# JacdacEc30Hub10x40_114.net
KiCad netlist of a schematic drawn in Altium Designer
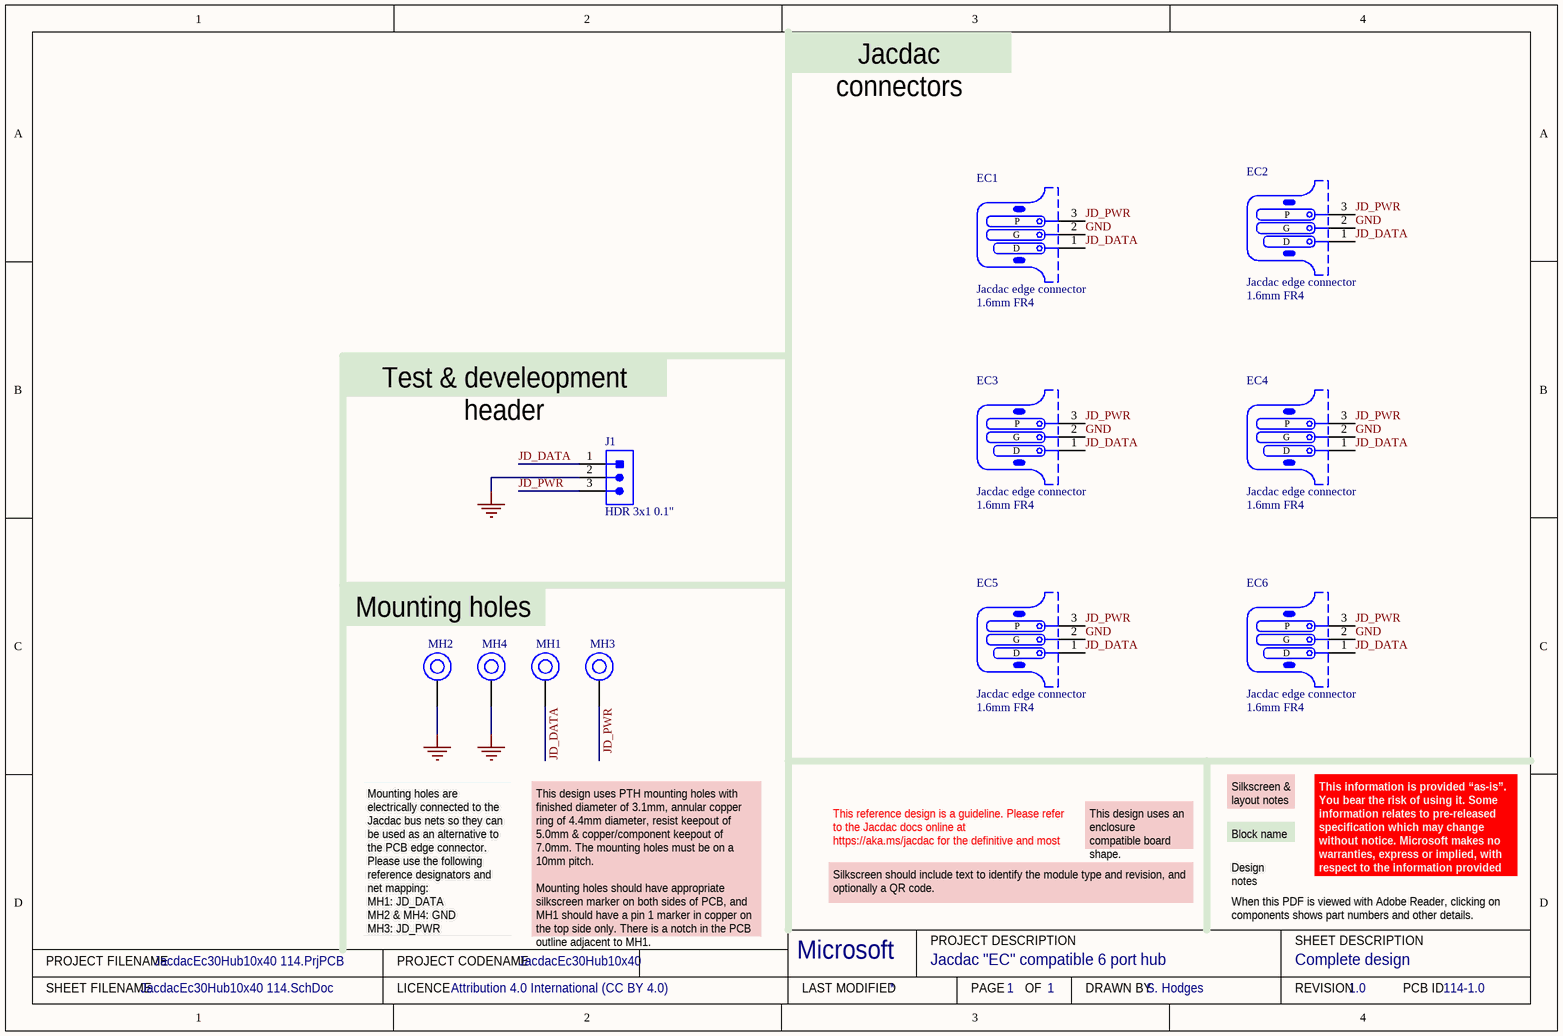
[diagram p0: JacdacEc30Hub10x40 114.SchDoc]

(export (version "E")
  (design (tool "Eeschema 10.0.6"))
  (components
    (comp (ref "EC1")
      (value "Jacdac edge connector")
      (footprint "Jacdac_edge_connector:JACDAC_EDGE_CONNECTOR_TRACES_0.15MM")
      (description "3 pin Jacdac edge connector 1.27mm pitch")
      (fields
        (field (name "MANUFACTURER PART NUMBER") "n/a")
        (field (name "PCB TYPE") "1.6mm FR4")
        (field (name "CREATED BY") "D. Gakure & S. Hodges")
      )
      (libsource (lib "generic-con") (part "Jacdac edge connector"))
    )
    (comp (ref "EC2")
      (value "Jacdac edge connector")
      (footprint "Jacdac_edge_connector:JACDAC_EDGE_CONNECTOR_TRACES_0.15MM")
      (description "3 pin Jacdac edge connector 1.27mm pitch")
      (fields
        (field (name "MANUFACTURER PART NUMBER") "n/a")
        (field (name "PCB TYPE") "1.6mm FR4")
        (field (name "CREATED BY") "D. Gakure & S. Hodges")
      )
      (libsource (lib "generic-con") (part "Jacdac edge connector"))
    )
    (comp (ref "EC3")
      (value "Jacdac edge connector")
      (footprint "Jacdac_edge_connector:JACDAC_EDGE_CONNECTOR_TRACES_0.15MM")
      (description "3 pin Jacdac edge connector 1.27mm pitch")
      (fields
        (field (name "MANUFACTURER PART NUMBER") "n/a")
        (field (name "PCB TYPE") "1.6mm FR4")
        (field (name "CREATED BY") "D. Gakure & S. Hodges")
      )
      (libsource (lib "generic-con") (part "Jacdac edge connector"))
    )
    (comp (ref "EC4")
      (value "Jacdac edge connector")
      (footprint "Jacdac_edge_connector:JACDAC_EDGE_CONNECTOR_TRACES_0.15MM")
      (description "3 pin Jacdac edge connector 1.27mm pitch")
      (fields
        (field (name "MANUFACTURER PART NUMBER") "n/a")
        (field (name "PCB TYPE") "1.6mm FR4")
        (field (name "CREATED BY") "D. Gakure & S. Hodges")
      )
      (libsource (lib "generic-con") (part "Jacdac edge connector"))
    )
    (comp (ref "EC5")
      (value "Jacdac edge connector")
      (footprint "Jacdac_edge_connector:JACDAC_EDGE_CONNECTOR_TRACES_0.15MM")
      (description "3 pin Jacdac edge connector 1.27mm pitch")
      (fields
        (field (name "MANUFACTURER PART NUMBER") "n/a")
        (field (name "PCB TYPE") "1.6mm FR4")
        (field (name "CREATED BY") "D. Gakure & S. Hodges")
      )
      (libsource (lib "generic-con") (part "Jacdac edge connector"))
    )
    (comp (ref "EC6")
      (value "Jacdac edge connector")
      (footprint "Jacdac_edge_connector:JACDAC_EDGE_CONNECTOR_TRACES_0.15MM")
      (description "3 pin Jacdac edge connector 1.27mm pitch")
      (fields
        (field (name "MANUFACTURER PART NUMBER") "n/a")
        (field (name "PCB TYPE") "1.6mm FR4")
        (field (name "CREATED BY") "D. Gakure & S. Hodges")
      )
      (libsource (lib "generic-con") (part "Jacdac edge connector"))
    )
    (comp (ref "J1")
      (value "HDR 3x1 0.1\"")
      (footprint "generic-con-0.1inch:Generic 1x3 2.54mm header")
      (description "2.54mm, 3x1 way, vertical, square pin, gold plate")
      (fields
        (field (name "MANUFACTURER") "Multicomp")
        (field (name "MANUFACTURER PART NUMBER") "2211S-03G")
        (field (name "CREATED BY") "daclethe")
      )
      (libsource (lib "generic-con") (part "Header Multicomp 2211S-03G-whitesch"))
    )
    (comp (ref "MH1")
      (value "MH_6.5MMK_4.5MMC_3.0MMD_PTH")
      (footprint "MH_6.5MMK_4.5MMC_3.0MMD_PTH")
      (description "Mounting Hole 6.5mm keepout, 4.5mm annualar ring and 3.0mm Drill PTH")
      (libsource (lib "generic") (part "MH_6.5MMK_4.5MMC_3.0MMD_PTH"))
    )
    (comp (ref "MH2")
      (value "MH_6.5MMK_4.5MMC_3.0MMD_PTH")
      (footprint "MH_6.5MMK_4.5MMC_3.0MMD_PTH")
      (description "Mounting Hole 6.5mm keepout, 4.5mm annualar ring and 3.0mm Drill PTH")
      (libsource (lib "generic") (part "MH_6.5MMK_4.5MMC_3.0MMD_PTH"))
    )
    (comp (ref "MH3")
      (value "MH_6.5MMK_4.5MMC_3.0MMD_PTH")
      (footprint "MH_6.5MMK_4.5MMC_3.0MMD_PTH")
      (description "Mounting Hole 6.5mm keepout, 4.5mm annualar ring and 3.0mm Drill PTH")
      (libsource (lib "generic") (part "MH_6.5MMK_4.5MMC_3.0MMD_PTH"))
    )
    (comp (ref "MH4")
      (value "MH_6.5MMK_4.5MMC_3.0MMD_PTH")
      (footprint "MH_6.5MMK_4.5MMC_3.0MMD_PTH")
      (description "Mounting Hole 6.5mm keepout, 4.5mm annualar ring and 3.0mm Drill PTH")
      (libsource (lib "generic") (part "MH_6.5MMK_4.5MMC_3.0MMD_PTH"))
    )
  )
  (nets
    (net (code "1") (name "/JD_DATA") (class "Default")
      (node (ref "EC1") (pin "1") (pinfunction "D_1") (pintype "passive"))
      (node (ref "EC2") (pin "1") (pinfunction "D_1") (pintype "passive"))
      (node (ref "EC3") (pin "1") (pinfunction "D_1") (pintype "passive"))
      (node (ref "EC4") (pin "1") (pinfunction "D_1") (pintype "passive"))
      (node (ref "EC5") (pin "1") (pinfunction "D_1") (pintype "passive"))
      (node (ref "EC6") (pin "1") (pinfunction "D_1") (pintype "passive"))
      (node (ref "J1") (pin "1") (pinfunction "1_1") (pintype "passive"))
      (node (ref "MH1") (pin "1") (pinfunction "1_1") (pintype "passive"))
    )
    (net (code "2") (name "/JD_PWR") (class "Default")
      (node (ref "EC1") (pin "3") (pinfunction "P_3") (pintype "passive"))
      (node (ref "EC2") (pin "3") (pinfunction "P_3") (pintype "passive"))
      (node (ref "EC3") (pin "3") (pinfunction "P_3") (pintype "passive"))
      (node (ref "EC4") (pin "3") (pinfunction "P_3") (pintype "passive"))
      (node (ref "EC5") (pin "3") (pinfunction "P_3") (pintype "passive"))
      (node (ref "EC6") (pin "3") (pinfunction "P_3") (pintype "passive"))
      (node (ref "J1") (pin "3") (pinfunction "3_3") (pintype "passive"))
      (node (ref "MH3") (pin "1") (pinfunction "1_1") (pintype "passive"))
    )
    (net (code "3") (name "GND") (class "Default")
      (node (ref "EC1") (pin "2") (pinfunction "G_2") (pintype "passive"))
      (node (ref "EC2") (pin "2") (pinfunction "G_2") (pintype "passive"))
      (node (ref "EC3") (pin "2") (pinfunction "G_2") (pintype "passive"))
      (node (ref "EC4") (pin "2") (pinfunction "G_2") (pintype "passive"))
      (node (ref "EC5") (pin "2") (pinfunction "G_2") (pintype "passive"))
      (node (ref "EC6") (pin "2") (pinfunction "G_2") (pintype "passive"))
      (node (ref "J1") (pin "2") (pinfunction "2_2") (pintype "passive"))
      (node (ref "MH2") (pin "1") (pinfunction "1_1") (pintype "passive"))
      (node (ref "MH4") (pin "1") (pinfunction "1_1") (pintype "passive"))
    )
  )
)
